# cadiz_mb_20140331_6.net
KiCad netlist of a schematic drawn in EAGLE
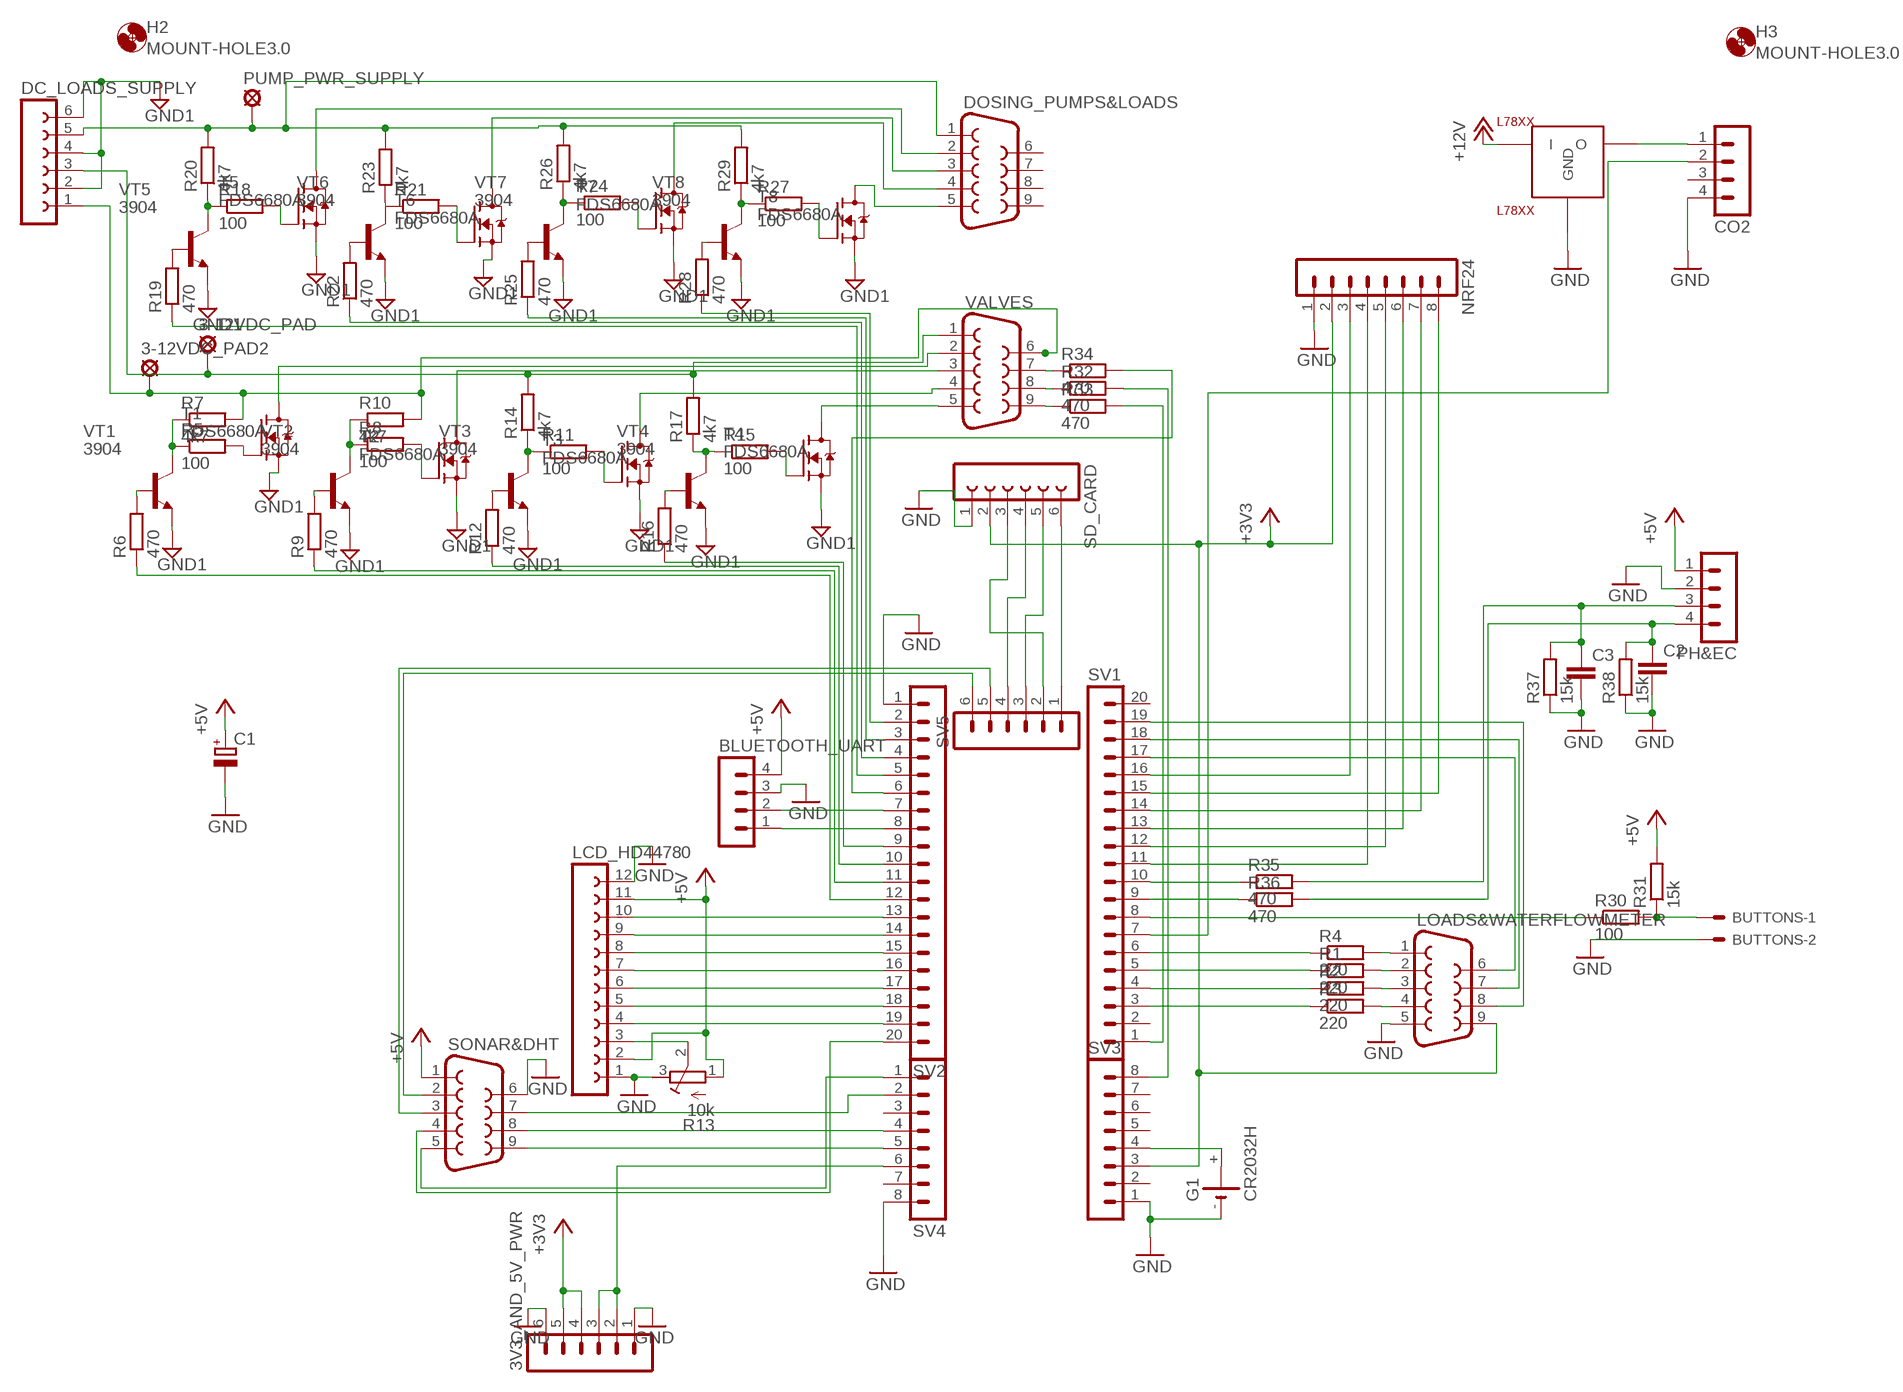
[diagram p0: schematic, sheet 1]

(export (version "E")
  (design (tool "Eeschema 10.0.6"))
  (components
    (comp (ref "3-12VDC_PAD")
      (value "LSP13")
      (footprint "eagle-import:LSP13")
      (libsource (lib "eagle-import") (part "LSP13"))
    )
    (comp (ref "3-12VDC_PAD2")
      (value "LSP13")
      (footprint "eagle-import:LSP13")
      (libsource (lib "eagle-import") (part "LSP13"))
    )
    (comp (ref "3V3_AND_5V_PWR")
      (value "MA06-1")
      (footprint "eagle-import:MA06-1")
      (libsource (lib "eagle-import") (part "MA06-1"))
    )
    (comp (ref "BLUETOOTH_UART")
      (value "MA04-1")
      (footprint "eagle-import:MA04-1")
      (libsource (lib "eagle-import") (part "MA04-1"))
    )
    (comp (ref "BUTTONS")
      (value "22-23-2021")
      (footprint "eagle-import:22-23-2021")
      (fields (field (name "MF") "MOLEX"))
      (libsource (lib "eagle-import") (part "22-23-2021"))
    )
    (comp (ref "C1")
      (value "CPOL-EUE5-13")
      (footprint "eagle-import:E5-13")
      (libsource (lib "eagle-import") (part "CPOL-EUE5-13"))
    )
    (comp (ref "C2")
      (value "C-EUC1206")
      (footprint "eagle-import:C1206")
      (libsource (lib "eagle-import") (part "C-EUC1206"))
    )
    (comp (ref "C3")
      (value "C-EUC1206")
      (footprint "eagle-import:C1206")
      (libsource (lib "eagle-import") (part "C-EUC1206"))
    )
    (comp (ref "CO2")
      (value "MA04-1")
      (footprint "eagle-import:MA04-1")
      (fields (field (name "OC_FARNELL") "unknown") (field (name "OC_NEWARK") "unknown"))
      (libsource (lib "eagle-import") (part "MA04-1"))
    )
    (comp (ref "DC_LOADS_SUPPLY")
      (value "FE06-1")
      (footprint "eagle-import:FE06")
      (libsource (lib "eagle-import") (part "FE06-1"))
    )
    (comp (ref "DOSING_PUMPS&LOADS")
      (value "F09HP")
      (footprint "eagle-import:F09HP")
      (libsource (lib "eagle-import") (part "F09HP"))
    )
    (comp (ref "G1")
      (value "CR2032H")
      (footprint "eagle-import:CR2032H")
      (libsource (lib "eagle-import") (part "CR2032H"))
    )
    (comp (ref "H2")
      (value "MOUNT-HOLE3.0")
      (footprint "eagle-import:3,0")
      (libsource (lib "eagle-import") (part "MOUNT-HOLE3.0"))
    )
    (comp (ref "H3")
      (value "MOUNT-HOLE3.0")
      (footprint "eagle-import:3,0")
      (libsource (lib "eagle-import") (part "MOUNT-HOLE3.0"))
    )
    (comp (ref "L7806")
      (value "L78XX")
      (footprint "eagle-import:TO220")
      (libsource (lib "eagle-import") (part "L78XX"))
    )
    (comp (ref "LCD_HD44780")
      (value "FE12-1")
      (footprint "eagle-import:FE12")
      (libsource (lib "eagle-import") (part "FE12-1"))
    )
    (comp (ref "LOADS&WATERFLOWMETER")
      (value "F09HP")
      (footprint "eagle-import:F09HP")
      (libsource (lib "eagle-import") (part "F09HP"))
    )
    (comp (ref "NRF24")
      (value "MA08-1")
      (footprint "eagle-import:MA08-1")
      (libsource (lib "eagle-import") (part "MA08-1"))
    )
    (comp (ref "PH&EC")
      (value "MA04-1")
      (footprint "eagle-import:MA04-1")
      (fields (field (name "OC_FARNELL") "unknown") (field (name "OC_NEWARK") "unknown"))
      (libsource (lib "eagle-import") (part "MA04-1"))
    )
    (comp (ref "PUMP_PWR_SUPPLY")
      (value "LSP13")
      (footprint "eagle-import:LSP13")
      (libsource (lib "eagle-import") (part "LSP13"))
    )
    (comp (ref "R1")
      (value "220")
      (footprint "eagle-import:M1206")
      (libsource (lib "eagle-import") (part "R-EU_M1206"))
    )
    (comp (ref "R2")
      (value "220")
      (footprint "eagle-import:M1206")
      (libsource (lib "eagle-import") (part "R-EU_M1206"))
    )
    (comp (ref "R3")
      (value "220")
      (footprint "eagle-import:M1206")
      (libsource (lib "eagle-import") (part "R-EU_M1206"))
    )
    (comp (ref "R4")
      (value "220")
      (footprint "eagle-import:M1206")
      (libsource (lib "eagle-import") (part "R-EU_M1206"))
    )
    (comp (ref "R5")
      (value "100")
      (footprint "eagle-import:M1206")
      (libsource (lib "eagle-import") (part "R-EU_M1206"))
    )
    (comp (ref "R6")
      (value "470")
      (footprint "eagle-import:M1206")
      (libsource (lib "eagle-import") (part "R-EU_M1206"))
    )
    (comp (ref "R7")
      (value "4k7")
      (footprint "eagle-import:M1206")
      (libsource (lib "eagle-import") (part "R-EU_M1206"))
    )
    (comp (ref "R8")
      (value "100")
      (footprint "eagle-import:M1206")
      (libsource (lib "eagle-import") (part "R-EU_M1206"))
    )
    (comp (ref "R9")
      (value "470")
      (footprint "eagle-import:M1206")
      (libsource (lib "eagle-import") (part "R-EU_M1206"))
    )
    (comp (ref "R10")
      (value "4k7")
      (footprint "eagle-import:M1206")
      (libsource (lib "eagle-import") (part "R-EU_M1206"))
    )
    (comp (ref "R11")
      (value "100")
      (footprint "eagle-import:M1206")
      (libsource (lib "eagle-import") (part "R-EU_M1206"))
    )
    (comp (ref "R12")
      (value "470")
      (footprint "eagle-import:M1206")
      (libsource (lib "eagle-import") (part "R-EU_M1206"))
    )
    (comp (ref "R13")
      (value "10k")
      (footprint "eagle-import:RTRIM3374")
      (libsource (lib "eagle-import") (part "R-TRIMM3374"))
    )
    (comp (ref "R14")
      (value "4k7")
      (footprint "eagle-import:M1206")
      (libsource (lib "eagle-import") (part "R-EU_M1206"))
    )
    (comp (ref "R15")
      (value "100")
      (footprint "eagle-import:M1206")
      (libsource (lib "eagle-import") (part "R-EU_M1206"))
    )
    (comp (ref "R16")
      (value "470")
      (footprint "eagle-import:M1206")
      (libsource (lib "eagle-import") (part "R-EU_M1206"))
    )
    (comp (ref "R17")
      (value "4k7")
      (footprint "eagle-import:M1206")
      (libsource (lib "eagle-import") (part "R-EU_M1206"))
    )
    (comp (ref "R18")
      (value "100")
      (footprint "eagle-import:M1206")
      (libsource (lib "eagle-import") (part "R-EU_M1206"))
    )
    (comp (ref "R19")
      (value "470")
      (footprint "eagle-import:M1206")
      (libsource (lib "eagle-import") (part "R-EU_M1206"))
    )
    (comp (ref "R20")
      (value "4k7")
      (footprint "eagle-import:M1206")
      (libsource (lib "eagle-import") (part "R-EU_M1206"))
    )
    (comp (ref "R21")
      (value "100")
      (footprint "eagle-import:M1206")
      (libsource (lib "eagle-import") (part "R-EU_M1206"))
    )
    (comp (ref "R22")
      (value "470")
      (footprint "eagle-import:M1206")
      (libsource (lib "eagle-import") (part "R-EU_M1206"))
    )
    (comp (ref "R23")
      (value "4k7")
      (footprint "eagle-import:M1206")
      (libsource (lib "eagle-import") (part "R-EU_M1206"))
    )
    (comp (ref "R24")
      (value "100")
      (footprint "eagle-import:M1206")
      (libsource (lib "eagle-import") (part "R-EU_M1206"))
    )
    (comp (ref "R25")
      (value "470")
      (footprint "eagle-import:M1206")
      (libsource (lib "eagle-import") (part "R-EU_M1206"))
    )
    (comp (ref "R26")
      (value "4k7")
      (footprint "eagle-import:M1206")
      (libsource (lib "eagle-import") (part "R-EU_M1206"))
    )
    (comp (ref "R27")
      (value "100")
      (footprint "eagle-import:M1206")
      (libsource (lib "eagle-import") (part "R-EU_M1206"))
    )
    (comp (ref "R28")
      (value "470")
      (footprint "eagle-import:M1206")
      (libsource (lib "eagle-import") (part "R-EU_M1206"))
    )
    (comp (ref "R29")
      (value "4k7")
      (footprint "eagle-import:M1206")
      (libsource (lib "eagle-import") (part "R-EU_M1206"))
    )
    (comp (ref "R30")
      (value "100")
      (footprint "eagle-import:M1206")
      (libsource (lib "eagle-import") (part "R-EU_M1206"))
    )
    (comp (ref "R31")
      (value "15k")
      (footprint "eagle-import:M1206")
      (libsource (lib "eagle-import") (part "R-EU_M1206"))
    )
    (comp (ref "R32")
      (value "470")
      (footprint "eagle-import:M1206")
      (libsource (lib "eagle-import") (part "R-EU_M1206"))
    )
    (comp (ref "R33")
      (value "470")
      (footprint "eagle-import:M1206")
      (libsource (lib "eagle-import") (part "R-EU_M1206"))
    )
    (comp (ref "R34")
      (value "470")
      (footprint "eagle-import:M1206")
      (libsource (lib "eagle-import") (part "R-EU_M1206"))
    )
    (comp (ref "R35")
      (value "470")
      (footprint "eagle-import:M1206")
      (libsource (lib "eagle-import") (part "R-EU_M1206"))
    )
    (comp (ref "R36")
      (value "470")
      (footprint "eagle-import:M1206")
      (libsource (lib "eagle-import") (part "R-EU_M1206"))
    )
    (comp (ref "R37")
      (value "15k")
      (footprint "eagle-import:M1206")
      (libsource (lib "eagle-import") (part "R-EU_M1206"))
    )
    (comp (ref "R38")
      (value "15k")
      (footprint "eagle-import:M1206")
      (libsource (lib "eagle-import") (part "R-EU_M1206"))
    )
    (comp (ref "SD_CARD")
      (value "FE06-1")
      (footprint "eagle-import:FE06")
      (libsource (lib "eagle-import") (part "FE06-1"))
    )
    (comp (ref "SONAR&DHT")
      (value "F09HP")
      (footprint "eagle-import:F09HP")
      (libsource (lib "eagle-import") (part "F09HP"))
    )
    (comp (ref "SV1")
      (value "MA20-1")
      (footprint "eagle-import:MA20-1")
      (libsource (lib "eagle-import") (part "MA20-1"))
    )
    (comp (ref "SV2")
      (value "MA20-1")
      (footprint "eagle-import:MA20-1")
      (libsource (lib "eagle-import") (part "MA20-1"))
    )
    (comp (ref "SV3")
      (value "MA08-1")
      (footprint "eagle-import:MA08-1")
      (libsource (lib "eagle-import") (part "MA08-1"))
    )
    (comp (ref "SV4")
      (value "MA08-1")
      (footprint "eagle-import:MA08-1")
      (libsource (lib "eagle-import") (part "MA08-1"))
    )
    (comp (ref "SV5")
      (value "MA06-1")
      (footprint "eagle-import:MA06-1")
      (libsource (lib "eagle-import") (part "MA06-1"))
    )
    (comp (ref "T1")
      (value "FDS6680A")
      (footprint "eagle-import:SO8")
      (libsource (lib "eagle-import") (part "FDS6680A_SOP8"))
    )
    (comp (ref "T2")
      (value "FDS6680A")
      (footprint "eagle-import:SO8")
      (libsource (lib "eagle-import") (part "FDS6680A_SOP8"))
    )
    (comp (ref "T3")
      (value "FDS6680A")
      (footprint "eagle-import:SO8")
      (libsource (lib "eagle-import") (part "FDS6680A_SOP8"))
    )
    (comp (ref "T4")
      (value "FDS6680A")
      (footprint "eagle-import:SO8")
      (libsource (lib "eagle-import") (part "FDS6680A_SOP8"))
    )
    (comp (ref "T5")
      (value "FDS6680A")
      (footprint "eagle-import:SO8")
      (libsource (lib "eagle-import") (part "FDS6680A_SOP8"))
    )
    (comp (ref "T6")
      (value "FDS6680A")
      (footprint "eagle-import:SO8")
      (libsource (lib "eagle-import") (part "FDS6680A_SOP8"))
    )
    (comp (ref "T7")
      (value "FDS6680A")
      (footprint "eagle-import:SO8")
      (libsource (lib "eagle-import") (part "FDS6680A_SOP8"))
    )
    (comp (ref "T8")
      (value "FDS6680A")
      (footprint "eagle-import:SO8")
      (libsource (lib "eagle-import") (part "FDS6680A_SOP8"))
    )
    (comp (ref "VALVES")
      (value "F09HP")
      (footprint "eagle-import:F09HP")
      (libsource (lib "eagle-import") (part "F09HP"))
    )
    (comp (ref "VT1")
      (value "3904")
      (footprint "eagle-import:SOT23")
      (libsource (lib "eagle-import") (part "BC847"))
    )
    (comp (ref "VT2")
      (value "3904")
      (footprint "eagle-import:SOT23")
      (libsource (lib "eagle-import") (part "BC847"))
    )
    (comp (ref "VT3")
      (value "3904")
      (footprint "eagle-import:SOT23")
      (libsource (lib "eagle-import") (part "BC847"))
    )
    (comp (ref "VT4")
      (value "3904")
      (footprint "eagle-import:SOT23")
      (libsource (lib "eagle-import") (part "BC847"))
    )
    (comp (ref "VT5")
      (value "3904")
      (footprint "eagle-import:SOT23")
      (libsource (lib "eagle-import") (part "BC847"))
    )
    (comp (ref "VT6")
      (value "3904")
      (footprint "eagle-import:SOT23")
      (libsource (lib "eagle-import") (part "BC847"))
    )
    (comp (ref "VT7")
      (value "3904")
      (footprint "eagle-import:SOT23")
      (libsource (lib "eagle-import") (part "BC847"))
    )
    (comp (ref "VT8")
      (value "3904")
      (footprint "eagle-import:SOT23")
      (libsource (lib "eagle-import") (part "BC847"))
    )
  )
  (nets
    (net (code "1") (name "+3V3") (class "Default")
      (node (ref "3V3_AND_5V_PWR") (pin "4") (pinfunction "4_4") (pintype "passive"))
      (node (ref "3V3_AND_5V_PWR") (pin "5") (pinfunction "5_5") (pintype "passive"))
      (node (ref "LOADS&WATERFLOWMETER") (pin "9") (pinfunction "9_9") (pintype "passive"))
      (node (ref "NRF24") (pin "2") (pinfunction "2_2") (pintype "passive"))
      (node (ref "SD_CARD") (pin "2") (pinfunction "2_2") (pintype "passive"))
      (node (ref "SV3") (pin "3") (pinfunction "3_3") (pintype "passive"))
    )
    (net (code "2") (name "+5V") (class "Default")
      (node (ref "BLUETOOTH_UART") (pin "4") (pinfunction "4_4") (pintype "passive"))
      (node (ref "C1") (pin "+") (pinfunction "+_+") (pintype "passive"))
      (node (ref "LCD_HD44780") (pin "11") (pinfunction "11_11") (pintype "passive"))
      (node (ref "LCD_HD44780") (pin "2") (pinfunction "2_2") (pintype "passive"))
      (node (ref "PH&EC") (pin "1") (pinfunction "1_1") (pintype "passive"))
      (node (ref "R13") (pin "1") (pinfunction "E_1") (pintype "passive"))
      (node (ref "R31") (pin "2") (pinfunction "2_2") (pintype "passive"))
      (node (ref "SONAR&DHT") (pin "1") (pinfunction "1_1") (pintype "passive"))
    )
    (net (code "3") (name "+12V") (class "Default")
      (node (ref "L7806") (pin "IN") (pinfunction "I_IN") (pintype "power_in"))
    )
    (net (code "4") (name "GND") (class "Default")
      (node (ref "3V3_AND_5V_PWR") (pin "1") (pinfunction "1_1") (pintype "passive"))
      (node (ref "3V3_AND_5V_PWR") (pin "6") (pinfunction "6_6") (pintype "passive"))
      (node (ref "BLUETOOTH_UART") (pin "3") (pinfunction "3_3") (pintype "passive"))
      (node (ref "BUTTONS") (pin "2") (pinfunction "S_2") (pintype "passive"))
      (node (ref "C1") (pin "-") (pinfunction "-_-") (pintype "passive"))
      (node (ref "C2") (pin "2") (pinfunction "2_2") (pintype "passive"))
      (node (ref "C3") (pin "2") (pinfunction "2_2") (pintype "passive"))
      (node (ref "CO2") (pin "4") (pinfunction "4_4") (pintype "passive"))
      (node (ref "G1") (pin "-") (pinfunction "-_-") (pintype "passive"))
      (node (ref "L7806") (pin "GND") (pinfunction "GND_GND") (pintype "power_in"))
      (node (ref "LCD_HD44780") (pin "1") (pinfunction "1_1") (pintype "passive"))
      (node (ref "LCD_HD44780") (pin "12") (pinfunction "12_12") (pintype "passive"))
      (node (ref "LOADS&WATERFLOWMETER") (pin "5") (pinfunction "5_5") (pintype "passive"))
      (node (ref "NRF24") (pin "1") (pinfunction "1_1") (pintype "passive"))
      (node (ref "PH&EC") (pin "2") (pinfunction "2_2") (pintype "passive"))
      (node (ref "R13") (pin "3") (pinfunction "A_3") (pintype "passive"))
      (node (ref "R37") (pin "1") (pinfunction "1_1") (pintype "passive"))
      (node (ref "R38") (pin "1") (pinfunction "1_1") (pintype "passive"))
      (node (ref "SD_CARD") (pin "1") (pinfunction "1_1") (pintype "passive"))
      (node (ref "SONAR&DHT") (pin "6") (pinfunction "6_6") (pintype "passive"))
      (node (ref "SV2") (pin "1") (pinfunction "1_1") (pintype "passive"))
      (node (ref "SV3") (pin "1") (pinfunction "1_1") (pintype "passive"))
      (node (ref "SV4") (pin "8") (pinfunction "8_8") (pintype "passive"))
    )
    (net (code "5") (name "GND1") (class "Default")
      (node (ref "DC_LOADS_SUPPLY") (pin "2") (pinfunction "2_2") (pintype "passive"))
      (node (ref "DC_LOADS_SUPPLY") (pin "4") (pinfunction "4_4") (pintype "passive"))
      (node (ref "DC_LOADS_SUPPLY") (pin "6") (pinfunction "6_6") (pintype "passive"))
      (node (ref "T1") (pin "SOURCE") (pinfunction "S_SOURCE") (pintype "passive"))
      (node (ref "T2") (pin "SOURCE") (pinfunction "S_SOURCE") (pintype "passive"))
      (node (ref "T3") (pin "SOURCE") (pinfunction "S_SOURCE") (pintype "passive"))
      (node (ref "T4") (pin "SOURCE") (pinfunction "S_SOURCE") (pintype "passive"))
      (node (ref "T5") (pin "SOURCE") (pinfunction "S_SOURCE") (pintype "passive"))
      (node (ref "T6") (pin "SOURCE") (pinfunction "S_SOURCE") (pintype "passive"))
      (node (ref "T7") (pin "SOURCE") (pinfunction "S_SOURCE") (pintype "passive"))
      (node (ref "T8") (pin "SOURCE") (pinfunction "S_SOURCE") (pintype "passive"))
      (node (ref "VT1") (pin "2") (pinfunction "E_2") (pintype "passive"))
      (node (ref "VT2") (pin "2") (pinfunction "E_2") (pintype "passive"))
      (node (ref "VT3") (pin "2") (pinfunction "E_2") (pintype "passive"))
      (node (ref "VT4") (pin "2") (pinfunction "E_2") (pintype "passive"))
      (node (ref "VT5") (pin "2") (pinfunction "E_2") (pintype "passive"))
      (node (ref "VT6") (pin "2") (pinfunction "E_2") (pintype "passive"))
      (node (ref "VT7") (pin "2") (pinfunction "E_2") (pintype "passive"))
      (node (ref "VT8") (pin "2") (pinfunction "E_2") (pintype "passive"))
    )
    (net (code "6") (name "Net-(3-12VDC_PAD-PadMP)") (class "Default")
      (node (ref "3-12VDC_PAD") (pin "MP") (pinfunction "MP_MP") (pintype "passive"))
      (node (ref "DC_LOADS_SUPPLY") (pin "3") (pinfunction "3_3") (pintype "passive"))
      (node (ref "R14") (pin "2") (pinfunction "2_2") (pintype "passive"))
      (node (ref "R17") (pin "2") (pinfunction "2_2") (pintype "passive"))
      (node (ref "VALVES") (pin "1") (pinfunction "1_1") (pintype "passive"))
    )
    (net (code "7") (name "Net-(3-12VDC_PAD2-PadMP)") (class "Default")
      (node (ref "3-12VDC_PAD2") (pin "MP") (pinfunction "MP_MP") (pintype "passive"))
      (node (ref "DC_LOADS_SUPPLY") (pin "1") (pinfunction "1_1") (pintype "passive"))
      (node (ref "R10") (pin "2") (pinfunction "2_2") (pintype "passive"))
      (node (ref "R7") (pin "2") (pinfunction "2_2") (pintype "passive"))
      (node (ref "VALVES") (pin "6") (pinfunction "6_6") (pintype "passive"))
    )
    (net (code "8") (name "Net-(3V3_AND_5V_PWR-Pad2)") (class "Default")
      (node (ref "3V3_AND_5V_PWR") (pin "2") (pinfunction "2_2") (pintype "passive"))
      (node (ref "3V3_AND_5V_PWR") (pin "3") (pinfunction "3_3") (pintype "passive"))
      (node (ref "SV4") (pin "6") (pinfunction "6_6") (pintype "passive"))
    )
    (net (code "9") (name "Net-(BLUETOOTH_UART-Pad1)") (class "Default")
      (node (ref "BLUETOOTH_UART") (pin "1") (pinfunction "1_1") (pintype "passive"))
      (node (ref "SV2") (pin "8") (pinfunction "8_8") (pintype "passive"))
    )
    (net (code "10") (name "Net-(BLUETOOTH_UART-Pad2)") (class "Default")
      (node (ref "BLUETOOTH_UART") (pin "2") (pinfunction "2_2") (pintype "passive"))
      (node (ref "SV2") (pin "7") (pinfunction "7_7") (pintype "passive"))
    )
    (net (code "11") (name "Net-(BUTTONSA-S)") (class "Default")
      (node (ref "BUTTONS") (pin "1") (pinfunction "S_1") (pintype "passive"))
      (node (ref "R30") (pin "2") (pinfunction "2_2") (pintype "passive"))
      (node (ref "R31") (pin "1") (pinfunction "1_1") (pintype "passive"))
    )
    (net (code "12") (name "Net-(C2-Pad1)") (class "Default")
      (node (ref "C2") (pin "1") (pinfunction "1_1") (pintype "passive"))
      (node (ref "PH&EC") (pin "4") (pinfunction "4_4") (pintype "passive"))
      (node (ref "R36") (pin "2") (pinfunction "2_2") (pintype "passive"))
      (node (ref "R38") (pin "2") (pinfunction "2_2") (pintype "passive"))
    )
    (net (code "13") (name "Net-(C3-Pad1)") (class "Default")
      (node (ref "C3") (pin "1") (pinfunction "1_1") (pintype "passive"))
      (node (ref "PH&EC") (pin "3") (pinfunction "3_3") (pintype "passive"))
      (node (ref "R35") (pin "2") (pinfunction "2_2") (pintype "passive"))
      (node (ref "R37") (pin "2") (pinfunction "2_2") (pintype "passive"))
    )
    (net (code "14") (name "Net-(CO2-Pad2)") (class "Default")
      (node (ref "CO2") (pin "2") (pinfunction "2_2") (pintype "passive"))
      (node (ref "SV1") (pin "7") (pinfunction "7_7") (pintype "passive"))
    )
    (net (code "15") (name "Net-(DC_LOADS_SUPPLY-Pad5)") (class "Default")
      (node (ref "DC_LOADS_SUPPLY") (pin "5") (pinfunction "5_5") (pintype "passive"))
      (node (ref "DOSING_PUMPS&LOADS") (pin "1") (pinfunction "1_1") (pintype "passive"))
      (node (ref "PUMP_PWR_SUPPLY") (pin "MP") (pinfunction "MP_MP") (pintype "passive"))
      (node (ref "R20") (pin "2") (pinfunction "2_2") (pintype "passive"))
      (node (ref "R23") (pin "2") (pinfunction "2_2") (pintype "passive"))
      (node (ref "R26") (pin "2") (pinfunction "2_2") (pintype "passive"))
      (node (ref "R29") (pin "2") (pinfunction "2_2") (pintype "passive"))
    )
    (net (code "16") (name "Net-(G1-Pad+)") (class "Default")
      (node (ref "G1") (pin "+") (pinfunction "+_+") (pintype "passive"))
      (node (ref "SV3") (pin "4") (pinfunction "4_4") (pintype "passive"))
    )
    (net (code "17") (name "Net-(L7806-O)") (class "Default")
      (node (ref "CO2") (pin "1") (pinfunction "1_1") (pintype "passive"))
      (node (ref "L7806") (pin "OUT") (pinfunction "O_OUT") (pintype "power_in"))
    )
    (net (code "18") (name "Net-(LCD_HD44780-Pad4)") (class "Default")
      (node (ref "LCD_HD44780") (pin "4") (pinfunction "4_4") (pintype "passive"))
      (node (ref "SV2") (pin "19") (pinfunction "19_19") (pintype "passive"))
    )
    (net (code "19") (name "Net-(LCD_HD44780-Pad5)") (class "Default")
      (node (ref "LCD_HD44780") (pin "5") (pinfunction "5_5") (pintype "passive"))
      (node (ref "SV2") (pin "18") (pinfunction "18_18") (pintype "passive"))
    )
    (net (code "20") (name "Net-(LCD_HD44780-Pad6)") (class "Default")
      (node (ref "LCD_HD44780") (pin "6") (pinfunction "6_6") (pintype "passive"))
      (node (ref "SV2") (pin "17") (pinfunction "17_17") (pintype "passive"))
    )
    (net (code "21") (name "Net-(LCD_HD44780-Pad7)") (class "Default")
      (node (ref "LCD_HD44780") (pin "7") (pinfunction "7_7") (pintype "passive"))
      (node (ref "SV2") (pin "16") (pinfunction "16_16") (pintype "passive"))
    )
    (net (code "22") (name "Net-(LCD_HD44780-Pad8)") (class "Default")
      (node (ref "LCD_HD44780") (pin "8") (pinfunction "8_8") (pintype "passive"))
      (node (ref "SV2") (pin "15") (pinfunction "15_15") (pintype "passive"))
    )
    (net (code "23") (name "Net-(LCD_HD44780-Pad9)") (class "Default")
      (node (ref "LCD_HD44780") (pin "9") (pinfunction "9_9") (pintype "passive"))
      (node (ref "SV2") (pin "14") (pinfunction "14_14") (pintype "passive"))
    )
    (net (code "24") (name "Net-(LCD_HD44780-Pad10)") (class "Default")
      (node (ref "LCD_HD44780") (pin "10") (pinfunction "10_10") (pintype "passive"))
      (node (ref "SV2") (pin "13") (pinfunction "13_13") (pintype "passive"))
    )
    (net (code "25") (name "Net-(LOADS&WATERFLOWMETER-Pad1)") (class "Default")
      (node (ref "LOADS&WATERFLOWMETER") (pin "1") (pinfunction "1_1") (pintype "passive"))
      (node (ref "R4") (pin "2") (pinfunction "2_2") (pintype "passive"))
    )
    (net (code "26") (name "Net-(LOADS&WATERFLOWMETER-Pad2)") (class "Default")
      (node (ref "LOADS&WATERFLOWMETER") (pin "2") (pinfunction "2_2") (pintype "passive"))
      (node (ref "R1") (pin "2") (pinfunction "2_2") (pintype "passive"))
    )
    (net (code "27") (name "Net-(LOADS&WATERFLOWMETER-Pad3)") (class "Default")
      (node (ref "LOADS&WATERFLOWMETER") (pin "3") (pinfunction "3_3") (pintype "passive"))
      (node (ref "R2") (pin "2") (pinfunction "2_2") (pintype "passive"))
    )
    (net (code "28") (name "Net-(LOADS&WATERFLOWMETER-Pad4)") (class "Default")
      (node (ref "LOADS&WATERFLOWMETER") (pin "4") (pinfunction "4_4") (pintype "passive"))
      (node (ref "R3") (pin "2") (pinfunction "2_2") (pintype "passive"))
    )
    (net (code "29") (name "Net-(LOADS&WATERFLOWMETER-Pad6)") (class "Default")
      (node (ref "LOADS&WATERFLOWMETER") (pin "6") (pinfunction "6_6") (pintype "passive"))
      (node (ref "SV1") (pin "17") (pinfunction "17_17") (pintype "passive"))
    )
    (net (code "30") (name "Net-(LOADS&WATERFLOWMETER-Pad7)") (class "Default")
      (node (ref "LOADS&WATERFLOWMETER") (pin "7") (pinfunction "7_7") (pintype "passive"))
      (node (ref "SV1") (pin "18") (pinfunction "18_18") (pintype "passive"))
    )
    (net (code "31") (name "Net-(LOADS&WATERFLOWMETER-Pad8)") (class "Default")
      (node (ref "LOADS&WATERFLOWMETER") (pin "8") (pinfunction "8_8") (pintype "passive"))
      (node (ref "SV1") (pin "19") (pinfunction "19_19") (pintype "passive"))
    )
    (net (code "32") (name "Net-(NRF24-Pad3)") (class "Default")
      (node (ref "NRF24") (pin "3") (pinfunction "3_3") (pintype "passive"))
      (node (ref "SV1") (pin "16") (pinfunction "16_16") (pintype "passive"))
    )
    (net (code "33") (name "Net-(NRF24-Pad4)") (class "Default")
      (node (ref "NRF24") (pin "4") (pinfunction "4_4") (pintype "passive"))
      (node (ref "SV1") (pin "11") (pinfunction "11_11") (pintype "passive"))
    )
    (net (code "34") (name "Net-(NRF24-Pad5)") (class "Default")
      (node (ref "NRF24") (pin "5") (pinfunction "5_5") (pintype "passive"))
      (node (ref "SV1") (pin "12") (pinfunction "12_12") (pintype "passive"))
    )
    (net (code "35") (name "Net-(NRF24-Pad6)") (class "Default")
      (node (ref "NRF24") (pin "6") (pinfunction "6_6") (pintype "passive"))
      (node (ref "SV1") (pin "13") (pinfunction "13_13") (pintype "passive"))
    )
    (net (code "36") (name "Net-(NRF24-Pad7)") (class "Default")
      (node (ref "NRF24") (pin "7") (pinfunction "7_7") (pintype "passive"))
      (node (ref "SV1") (pin "14") (pinfunction "14_14") (pintype "passive"))
    )
    (net (code "37") (name "Net-(NRF24-Pad8)") (class "Default")
      (node (ref "NRF24") (pin "8") (pinfunction "8_8") (pintype "passive"))
      (node (ref "SV1") (pin "15") (pinfunction "15_15") (pintype "passive"))
    )
    (net (code "38") (name "Net-(R1-Pad1)") (class "Default")
      (node (ref "R1") (pin "1") (pinfunction "1_1") (pintype "passive"))
      (node (ref "SV1") (pin "5") (pinfunction "5_5") (pintype "passive"))
    )
    (net (code "39") (name "Net-(R2-Pad1)") (class "Default")
      (node (ref "R2") (pin "1") (pinfunction "1_1") (pintype "passive"))
      (node (ref "SV1") (pin "4") (pinfunction "4_4") (pintype "passive"))
    )
    (net (code "40") (name "Net-(R3-Pad1)") (class "Default")
      (node (ref "R3") (pin "1") (pinfunction "1_1") (pintype "passive"))
      (node (ref "SV1") (pin "3") (pinfunction "3_3") (pintype "passive"))
    )
    (net (code "41") (name "Net-(R4-Pad1)") (class "Default")
      (node (ref "R4") (pin "1") (pinfunction "1_1") (pintype "passive"))
      (node (ref "SV1") (pin "6") (pinfunction "6_6") (pintype "passive"))
    )
    (net (code "42") (name "Net-(R6-Pad1)") (class "Default")
      (node (ref "R6") (pin "1") (pinfunction "1_1") (pintype "passive"))
      (node (ref "SV2") (pin "12") (pinfunction "12_12") (pintype "passive"))
    )
    (net (code "43") (name "Net-(R9-Pad1)") (class "Default")
      (node (ref "R9") (pin "1") (pinfunction "1_1") (pintype "passive"))
      (node (ref "SV2") (pin "11") (pinfunction "11_11") (pintype "passive"))
    )
    (net (code "44") (name "Net-(R12-Pad1)") (class "Default")
      (node (ref "R12") (pin "1") (pinfunction "1_1") (pintype "passive"))
      (node (ref "SV2") (pin "10") (pinfunction "10_10") (pintype "passive"))
    )
    (net (code "45") (name "Net-(R13-S)") (class "Default")
      (node (ref "LCD_HD44780") (pin "3") (pinfunction "3_3") (pintype "passive"))
      (node (ref "R13") (pin "2") (pinfunction "S_2") (pintype "passive"))
    )
    (net (code "46") (name "Net-(R16-Pad1)") (class "Default")
      (node (ref "R16") (pin "1") (pinfunction "1_1") (pintype "passive"))
      (node (ref "SV2") (pin "9") (pinfunction "9_9") (pintype "passive"))
    )
    (net (code "47") (name "Net-(R19-Pad1)") (class "Default")
      (node (ref "R19") (pin "1") (pinfunction "1_1") (pintype "passive"))
      (node (ref "SV2") (pin "5") (pinfunction "5_5") (pintype "passive"))
    )
    (net (code "48") (name "Net-(R22-Pad1)") (class "Default")
      (node (ref "R22") (pin "1") (pinfunction "1_1") (pintype "passive"))
      (node (ref "SV2") (pin "4") (pinfunction "4_4") (pintype "passive"))
    )
    (net (code "49") (name "Net-(R25-Pad1)") (class "Default")
      (node (ref "R25") (pin "1") (pinfunction "1_1") (pintype "passive"))
      (node (ref "SV2") (pin "3") (pinfunction "3_3") (pintype "passive"))
    )
    (net (code "50") (name "Net-(R28-Pad1)") (class "Default")
      (node (ref "R28") (pin "1") (pinfunction "1_1") (pintype "passive"))
      (node (ref "SV2") (pin "2") (pinfunction "2_2") (pintype "passive"))
    )
    (net (code "51") (name "Net-(R30-Pad1)") (class "Default")
      (node (ref "R30") (pin "1") (pinfunction "1_1") (pintype "passive"))
      (node (ref "SV1") (pin "8") (pinfunction "8_8") (pintype "passive"))
    )
    (net (code "52") (name "Net-(R32-Pad1)") (class "Default")
      (node (ref "R32") (pin "1") (pinfunction "1_1") (pintype "passive"))
      (node (ref "VALVES") (pin "8") (pinfunction "8_8") (pintype "passive"))
    )
    (net (code "53") (name "Net-(R32-Pad2)") (class "Default")
      (node (ref "R32") (pin "2") (pinfunction "2_2") (pintype "passive"))
      (node (ref "SV3") (pin "8") (pinfunction "8_8") (pintype "passive"))
    )
    (net (code "54") (name "Net-(R33-Pad1)") (class "Default")
      (node (ref "R33") (pin "1") (pinfunction "1_1") (pintype "passive"))
      (node (ref "VALVES") (pin "9") (pinfunction "9_9") (pintype "passive"))
    )
    (net (code "55") (name "Net-(R33-Pad2)") (class "Default")
      (node (ref "R33") (pin "2") (pinfunction "2_2") (pintype "passive"))
      (node (ref "SV1") (pin "1") (pinfunction "1_1") (pintype "passive"))
    )
    (net (code "56") (name "Net-(R34-Pad1)") (class "Default")
      (node (ref "R34") (pin "1") (pinfunction "1_1") (pintype "passive"))
      (node (ref "VALVES") (pin "7") (pinfunction "7_7") (pintype "passive"))
    )
    (net (code "57") (name "Net-(R34-Pad2)") (class "Default")
      (node (ref "R34") (pin "2") (pinfunction "2_2") (pintype "passive"))
      (node (ref "SV2") (pin "6") (pinfunction "6_6") (pintype "passive"))
    )
    (net (code "58") (name "Net-(R35-Pad1)") (class "Default")
      (node (ref "R35") (pin "1") (pinfunction "1_1") (pintype "passive"))
      (node (ref "SV1") (pin "10") (pinfunction "10_10") (pintype "passive"))
    )
    (net (code "59") (name "Net-(R36-Pad1)") (class "Default")
      (node (ref "R36") (pin "1") (pinfunction "1_1") (pintype "passive"))
      (node (ref "SV1") (pin "9") (pinfunction "9_9") (pintype "passive"))
    )
    (net (code "60") (name "Net-(SD_CARD-Pad3)") (class "Default")
      (node (ref "SD_CARD") (pin "3") (pinfunction "3_3") (pintype "passive"))
      (node (ref "SV5") (pin "2") (pinfunction "2_2") (pintype "passive"))
    )
    (net (code "61") (name "Net-(SD_CARD-Pad4)") (class "Default")
      (node (ref "SD_CARD") (pin "4") (pinfunction "4_4") (pintype "passive"))
      (node (ref "SV5") (pin "4") (pinfunction "4_4") (pintype "passive"))
    )
    (net (code "62") (name "Net-(SD_CARD-Pad5)") (class "Default")
      (node (ref "SD_CARD") (pin "5") (pinfunction "5_5") (pintype "passive"))
      (node (ref "SV5") (pin "3") (pinfunction "3_3") (pintype "passive"))
    )
    (net (code "63") (name "Net-(SD_CARD-Pad6)") (class "Default")
      (node (ref "SD_CARD") (pin "6") (pinfunction "6_6") (pintype "passive"))
      (node (ref "SV5") (pin "1") (pinfunction "1_1") (pintype "passive"))
    )
    (net (code "64") (name "Net-(SONAR&DHT-Pad2)") (class "Default")
      (node (ref "SONAR&DHT") (pin "2") (pinfunction "2_2") (pintype "passive"))
      (node (ref "SV5") (pin "6") (pinfunction "6_6") (pintype "passive"))
    )
    (net (code "65") (name "Net-(SONAR&DHT-Pad3)") (class "Default")
      (node (ref "SONAR&DHT") (pin "3") (pinfunction "3_3") (pintype "passive"))
      (node (ref "SV5") (pin "5") (pinfunction "5_5") (pintype "passive"))
    )
    (net (code "66") (name "Net-(SONAR&DHT-Pad4)") (class "Default")
      (node (ref "SONAR&DHT") (pin "4") (pinfunction "4_4") (pintype "passive"))
      (node (ref "SV2") (pin "20") (pinfunction "20_20") (pintype "passive"))
    )
    (net (code "67") (name "Net-(SONAR&DHT-Pad5)") (class "Default")
      (node (ref "SONAR&DHT") (pin "5") (pinfunction "5_5") (pintype "passive"))
      (node (ref "SV4") (pin "1") (pinfunction "1_1") (pintype "passive"))
    )
    (net (code "68") (name "Net-(SONAR&DHT-Pad7)") (class "Default")
      (node (ref "SONAR&DHT") (pin "7") (pinfunction "7_7") (pintype "passive"))
      (node (ref "SV4") (pin "2") (pinfunction "2_2") (pintype "passive"))
    )
    (net (code "69") (name "Net-(SONAR&DHT-Pad8)") (class "Default")
      (node (ref "SONAR&DHT") (pin "8") (pinfunction "8_8") (pintype "passive"))
      (node (ref "SV4") (pin "4") (pinfunction "4_4") (pintype "passive"))
    )
    (net (code "70") (name "Net-(SONAR&DHT-Pad9)") (class "Default")
      (node (ref "SONAR&DHT") (pin "9") (pinfunction "9_9") (pintype "passive"))
      (node (ref "SV4") (pin "5") (pinfunction "5_5") (pintype "passive"))
    )
    (net (code "71") (name "Net-(T1-D)") (class "Default")
      (node (ref "T1") (pin "DRAIN") (pinfunction "D_DRAIN") (pintype "passive"))
      (node (ref "VALVES") (pin "2") (pinfunction "2_2") (pintype "passive"))
    )
    (net (code "72") (name "Net-(T1-G)") (class "Default")
      (node (ref "R5") (pin "2") (pinfunction "2_2") (pintype "passive"))
      (node (ref "T1") (pin "GATE") (pinfunction "G_GATE") (pintype "passive"))
    )
    (net (code "73") (name "Net-(T2-D)") (class "Default")
      (node (ref "T2") (pin "DRAIN") (pinfunction "D_DRAIN") (pintype "passive"))
      (node (ref "VALVES") (pin "3") (pinfunction "3_3") (pintype "passive"))
    )
    (net (code "74") (name "Net-(T2-G)") (class "Default")
      (node (ref "R8") (pin "2") (pinfunction "2_2") (pintype "passive"))
      (node (ref "T2") (pin "GATE") (pinfunction "G_GATE") (pintype "passive"))
    )
    (net (code "75") (name "Net-(T3-D)") (class "Default")
      (node (ref "T3") (pin "DRAIN") (pinfunction "D_DRAIN") (pintype "passive"))
      (node (ref "VALVES") (pin "4") (pinfunction "4_4") (pintype "passive"))
    )
    (net (code "76") (name "Net-(T3-G)") (class "Default")
      (node (ref "R11") (pin "2") (pinfunction "2_2") (pintype "passive"))
      (node (ref "T3") (pin "GATE") (pinfunction "G_GATE") (pintype "passive"))
    )
    (net (code "77") (name "Net-(T4-D)") (class "Default")
      (node (ref "T4") (pin "DRAIN") (pinfunction "D_DRAIN") (pintype "passive"))
      (node (ref "VALVES") (pin "5") (pinfunction "5_5") (pintype "passive"))
    )
    (net (code "78") (name "Net-(T4-G)") (class "Default")
      (node (ref "R15") (pin "2") (pinfunction "2_2") (pintype "passive"))
      (node (ref "T4") (pin "GATE") (pinfunction "G_GATE") (pintype "passive"))
    )
    (net (code "79") (name "Net-(T5-D)") (class "Default")
      (node (ref "DOSING_PUMPS&LOADS") (pin "2") (pinfunction "2_2") (pintype "passive"))
      (node (ref "T5") (pin "DRAIN") (pinfunction "D_DRAIN") (pintype "passive"))
    )
    (net (code "80") (name "Net-(T5-G)") (class "Default")
      (node (ref "R18") (pin "2") (pinfunction "2_2") (pintype "passive"))
      (node (ref "T5") (pin "GATE") (pinfunction "G_GATE") (pintype "passive"))
    )
    (net (code "81") (name "Net-(T6-D)") (class "Default")
      (node (ref "DOSING_PUMPS&LOADS") (pin "3") (pinfunction "3_3") (pintype "passive"))
      (node (ref "T6") (pin "DRAIN") (pinfunction "D_DRAIN") (pintype "passive"))
    )
    (net (code "82") (name "Net-(T6-G)") (class "Default")
      (node (ref "R21") (pin "2") (pinfunction "2_2") (pintype "passive"))
      (node (ref "T6") (pin "GATE") (pinfunction "G_GATE") (pintype "passive"))
    )
    (net (code "83") (name "Net-(T7-D)") (class "Default")
      (node (ref "DOSING_PUMPS&LOADS") (pin "4") (pinfunction "4_4") (pintype "passive"))
      (node (ref "T7") (pin "DRAIN") (pinfunction "D_DRAIN") (pintype "passive"))
    )
    (net (code "84") (name "Net-(T7-G)") (class "Default")
      (node (ref "R24") (pin "2") (pinfunction "2_2") (pintype "passive"))
      (node (ref "T7") (pin "GATE") (pinfunction "G_GATE") (pintype "passive"))
    )
    (net (code "85") (name "Net-(T8-D)") (class "Default")
      (node (ref "DOSING_PUMPS&LOADS") (pin "5") (pinfunction "5_5") (pintype "passive"))
      (node (ref "T8") (pin "DRAIN") (pinfunction "D_DRAIN") (pintype "passive"))
    )
    (net (code "86") (name "Net-(T8-G)") (class "Default")
      (node (ref "R27") (pin "2") (pinfunction "2_2") (pintype "passive"))
      (node (ref "T8") (pin "GATE") (pinfunction "G_GATE") (pintype "passive"))
    )
    (net (code "87") (name "Net-(VT1-B)") (class "Default")
      (node (ref "R6") (pin "2") (pinfunction "2_2") (pintype "passive"))
      (node (ref "VT1") (pin "1") (pinfunction "B_1") (pintype "passive"))
    )
    (net (code "88") (name "Net-(VT1-C)") (class "Default")
      (node (ref "R5") (pin "1") (pinfunction "1_1") (pintype "passive"))
      (node (ref "R7") (pin "1") (pinfunction "1_1") (pintype "passive"))
      (node (ref "VT1") (pin "3") (pinfunction "C_3") (pintype "passive"))
    )
    (net (code "89") (name "Net-(VT2-B)") (class "Default")
      (node (ref "R9") (pin "2") (pinfunction "2_2") (pintype "passive"))
      (node (ref "VT2") (pin "1") (pinfunction "B_1") (pintype "passive"))
    )
    (net (code "90") (name "Net-(VT2-C)") (class "Default")
      (node (ref "R10") (pin "1") (pinfunction "1_1") (pintype "passive"))
      (node (ref "R8") (pin "1") (pinfunction "1_1") (pintype "passive"))
      (node (ref "VT2") (pin "3") (pinfunction "C_3") (pintype "passive"))
    )
    (net (code "91") (name "Net-(VT3-B)") (class "Default")
      (node (ref "R12") (pin "2") (pinfunction "2_2") (pintype "passive"))
      (node (ref "VT3") (pin "1") (pinfunction "B_1") (pintype "passive"))
    )
    (net (code "92") (name "Net-(VT3-C)") (class "Default")
      (node (ref "R11") (pin "1") (pinfunction "1_1") (pintype "passive"))
      (node (ref "R14") (pin "1") (pinfunction "1_1") (pintype "passive"))
      (node (ref "VT3") (pin "3") (pinfunction "C_3") (pintype "passive"))
    )
    (net (code "93") (name "Net-(VT4-B)") (class "Default")
      (node (ref "R16") (pin "2") (pinfunction "2_2") (pintype "passive"))
      (node (ref "VT4") (pin "1") (pinfunction "B_1") (pintype "passive"))
    )
    (net (code "94") (name "Net-(VT4-C)") (class "Default")
      (node (ref "R15") (pin "1") (pinfunction "1_1") (pintype "passive"))
      (node (ref "R17") (pin "1") (pinfunction "1_1") (pintype "passive"))
      (node (ref "VT4") (pin "3") (pinfunction "C_3") (pintype "passive"))
    )
    (net (code "95") (name "Net-(VT5-B)") (class "Default")
      (node (ref "R19") (pin "2") (pinfunction "2_2") (pintype "passive"))
      (node (ref "VT5") (pin "1") (pinfunction "B_1") (pintype "passive"))
    )
    (net (code "96") (name "Net-(VT5-C)") (class "Default")
      (node (ref "R18") (pin "1") (pinfunction "1_1") (pintype "passive"))
      (node (ref "R20") (pin "1") (pinfunction "1_1") (pintype "passive"))
      (node (ref "VT5") (pin "3") (pinfunction "C_3") (pintype "passive"))
    )
    (net (code "97") (name "Net-(VT6-B)") (class "Default")
      (node (ref "R22") (pin "2") (pinfunction "2_2") (pintype "passive"))
      (node (ref "VT6") (pin "1") (pinfunction "B_1") (pintype "passive"))
    )
    (net (code "98") (name "Net-(VT6-C)") (class "Default")
      (node (ref "R21") (pin "1") (pinfunction "1_1") (pintype "passive"))
      (node (ref "R23") (pin "1") (pinfunction "1_1") (pintype "passive"))
      (node (ref "VT6") (pin "3") (pinfunction "C_3") (pintype "passive"))
    )
    (net (code "99") (name "Net-(VT7-B)") (class "Default")
      (node (ref "R25") (pin "2") (pinfunction "2_2") (pintype "passive"))
      (node (ref "VT7") (pin "1") (pinfunction "B_1") (pintype "passive"))
    )
    (net (code "100") (name "Net-(VT7-C)") (class "Default")
      (node (ref "R24") (pin "1") (pinfunction "1_1") (pintype "passive"))
      (node (ref "R26") (pin "1") (pinfunction "1_1") (pintype "passive"))
      (node (ref "VT7") (pin "3") (pinfunction "C_3") (pintype "passive"))
    )
    (net (code "101") (name "Net-(VT8-B)") (class "Default")
      (node (ref "R28") (pin "2") (pinfunction "2_2") (pintype "passive"))
      (node (ref "VT8") (pin "1") (pinfunction "B_1") (pintype "passive"))
    )
    (net (code "102") (name "Net-(VT8-C)") (class "Default")
      (node (ref "R27") (pin "1") (pinfunction "1_1") (pintype "passive"))
      (node (ref "R29") (pin "1") (pinfunction "1_1") (pintype "passive"))
      (node (ref "VT8") (pin "3") (pinfunction "C_3") (pintype "passive"))
    )
    (net (code "103") (name "unconnected-(CO2-Pad3)") (class "Default")
      (node (ref "CO2") (pin "3") (pinfunction "3_3") (pintype "passive"))
    )
    (net (code "104") (name "unconnected-(DOSING_PUMPS&LOADS-Pad6)") (class "Default")
      (node (ref "DOSING_PUMPS&LOADS") (pin "6") (pinfunction "6_6") (pintype "passive"))
    )
    (net (code "105") (name "unconnected-(DOSING_PUMPS&LOADS-Pad7)") (class "Default")
      (node (ref "DOSING_PUMPS&LOADS") (pin "7") (pinfunction "7_7") (pintype "passive"))
    )
    (net (code "106") (name "unconnected-(DOSING_PUMPS&LOADS-Pad8)") (class "Default")
      (node (ref "DOSING_PUMPS&LOADS") (pin "8") (pinfunction "8_8") (pintype "passive"))
    )
    (net (code "107") (name "unconnected-(DOSING_PUMPS&LOADS-Pad9)") (class "Default")
      (node (ref "DOSING_PUMPS&LOADS") (pin "9") (pinfunction "9_9") (pintype "passive"))
    )
    (net (code "108") (name "unconnected-(G1-+-Pad+@1)") (class "Default")
      (node (ref "G1") (pin "+@1") (pinfunction "+_+@1") (pintype "passive"))
    )
    (net (code "109") (name "unconnected-(SV1-Pad2)") (class "Default")
      (node (ref "SV1") (pin "2") (pinfunction "2_2") (pintype "passive"))
    )
    (net (code "110") (name "unconnected-(SV1-Pad20)") (class "Default")
      (node (ref "SV1") (pin "20") (pinfunction "20_20") (pintype "passive"))
    )
    (net (code "111") (name "unconnected-(SV3-Pad2)") (class "Default")
      (node (ref "SV3") (pin "2") (pinfunction "2_2") (pintype "passive"))
    )
    (net (code "112") (name "unconnected-(SV3-Pad5)") (class "Default")
      (node (ref "SV3") (pin "5") (pinfunction "5_5") (pintype "passive"))
    )
    (net (code "113") (name "unconnected-(SV3-Pad6)") (class "Default")
      (node (ref "SV3") (pin "6") (pinfunction "6_6") (pintype "passive"))
    )
    (net (code "114") (name "unconnected-(SV3-Pad7)") (class "Default")
      (node (ref "SV3") (pin "7") (pinfunction "7_7") (pintype "passive"))
    )
    (net (code "115") (name "unconnected-(SV4-Pad3)") (class "Default")
      (node (ref "SV4") (pin "3") (pinfunction "3_3") (pintype "passive"))
    )
    (net (code "116") (name "unconnected-(SV4-Pad7)") (class "Default")
      (node (ref "SV4") (pin "7") (pinfunction "7_7") (pintype "passive"))
    )
  )
)
